# LM60.net
KiCad netlist of a schematic drawn in Altium Designer
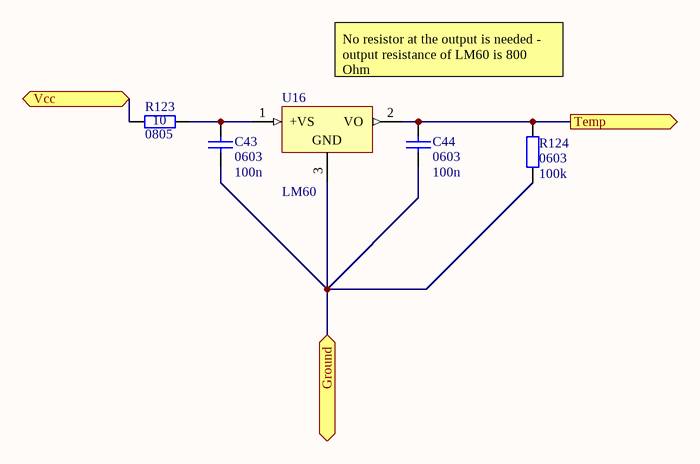
[diagram p0: LM60.SchDoc]

(export (version "E")
  (design (tool "Eeschema 10.0.6"))
  (components
    (comp (ref "C43")
      (value "0603")
      (footprint "SMD_Capacitor_0603")
      (description "Capacitor")
      (fields (field (name "ALTIUM_VALUE") "100n") (field (name "PUBLISHER") "Altium Limited"))
      (libsource (lib "Miscellaneous Devices") (part "Cap"))
    )
    (comp (ref "C44")
      (value "0603")
      (footprint "SMD_Capacitor_0603")
      (description "Capacitor")
      (fields (field (name "ALTIUM_VALUE") "100n") (field (name "PUBLISHER") "Altium Limited"))
      (libsource (lib "Miscellaneous Devices") (part "Cap"))
    )
    (comp (ref "R123")
      (value "0805")
      (footprint "SMD_Resistor_0805")
      (description "Resistor")
      (fields (field (name "ALTIUM_VALUE") "10") (field (name "PUBLISHER") "Altium Limited"))
      (libsource (lib "Miscellaneous Devices") (part "Res2"))
    )
    (comp (ref "R124")
      (value "0603")
      (footprint "SMD_Resistor_0603")
      (description "Resistor")
      (fields (field (name "ALTIUM_VALUE") "100k") (field (name "PUBLISHER") "Altium Limited"))
      (libsource (lib "") (part "Res2_1"))
    )
    (comp (ref "U16")
      (value "LM60")
      (footprint "SOT23-3")
      (description "Analog temperature sensor")
      (libsource (lib "microcircuits_other-functions") (part "LM60"))
    )
  )
  (nets
    (net (code "1") (name "/Ground") (class "Default")
      (node (ref "C43") (pin "1") (pinfunction "1_1") (pintype "passive"))
      (node (ref "C44") (pin "1") (pinfunction "1_1") (pintype "passive"))
      (node (ref "R124") (pin "1") (pinfunction "1_1") (pintype "passive"))
      (node (ref "U16") (pin "3") (pinfunction "GND_3") (pintype "power_in"))
    )
    (net (code "2") (name "/Temp") (class "Default")
      (node (ref "C44") (pin "2") (pinfunction "2_2") (pintype "passive"))
      (node (ref "R124") (pin "2") (pinfunction "2_2") (pintype "passive"))
      (node (ref "U16") (pin "2") (pinfunction "VO_2") (pintype "output"))
    )
    (net (code "3") (name "/Vcc") (class "Default")
      (node (ref "R123") (pin "1") (pinfunction "1_1") (pintype "passive"))
    )
    (net (code "4") (name "Net-(U16-+VS)") (class "Default")
      (node (ref "C43") (pin "2") (pinfunction "2_2") (pintype "passive"))
      (node (ref "R123") (pin "2") (pinfunction "2_2") (pintype "passive"))
      (node (ref "U16") (pin "1") (pinfunction "+VS_1") (pintype "input"))
    )
  )
)
